# LPCB235_-_WATCHDOG.net
KiCad netlist of a schematic drawn in Altium Designer
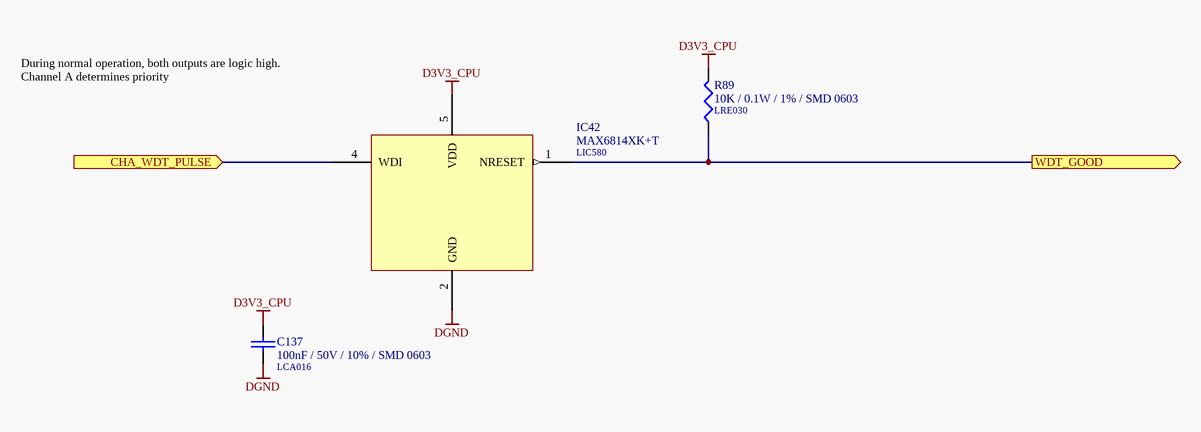
[diagram p0: LPCB235 - WATCHDOG.SchDoc]

(export (version "E")
  (design (tool "Eeschema 10.0.6"))
  (components
    (comp (ref "C137")
      (value "100nF / 50V / 10% / SMD 0603")
      (footprint "LFP011__CC1608-0603-IPC7351_B")
      (description "Capacitor, Ceramic Chip, 100nF (0.1uF), 50V, 5%, SMD 0603 [LCA016]")
      (fields (field (name "LDL_NUMBER") "LCA016"))
      (libsource (lib "LDL_Capacitors") (part "100nF / 50V / 10% / SMD 0603"))
    )
    (comp (ref "IC42")
      (value "MAX6814XK+T")
      (footprint "LFP047__SOT353")
      (description "IC, Watchdog, SMD [LIC580]")
      (fields (field (name "LDL_NUMBER") "LIC580"))
      (libsource (lib "LDL_Semiconductors") (part "MAX6814XK+T"))
    )
    (comp (ref "R89")
      (value "10K / 0.1W / 1% / SMD 0603")
      (footprint "LFP020__CR1608-0603-IPC7351_B")
      (description "Resistor, Ceramic Chip, 10K, 0.1W, 1%, SMD 0603 [LRE030]")
      (fields (field (name "LDL_NUMBER") "LRE030"))
      (libsource (lib "LDL_Resistors") (part "10K / 0.1W / 1% / SMD 0603"))
    )
  )
  (nets
    (net (code "1") (name "/CHA_WDT_PULSE") (class "Default")
      (node (ref "IC42") (pin "4") (pinfunction "WDI_4") (pintype "passive"))
    )
    (net (code "2") (name "/WDT_GOOD") (class "Default")
      (node (ref "IC42") (pin "1") (pinfunction "NRESET_1") (pintype "output"))
      (node (ref "R89") (pin "1") (pintype "passive"))
    )
    (net (code "3") (name "D3V3_CPU") (class "Default")
      (node (ref "C137") (pin "1") (pintype "passive"))
      (node (ref "IC42") (pin "5") (pinfunction "VDD_5") (pintype "power_in"))
      (node (ref "R89") (pin "2") (pintype "passive"))
    )
    (net (code "4") (name "DGND") (class "Default")
      (node (ref "C137") (pin "2") (pintype "passive"))
      (node (ref "IC42") (pin "2") (pinfunction "GND_2") (pintype "power_in"))
    )
  )
)
